# BSK2.net
KiCad netlist of a schematic drawn in EAGLE
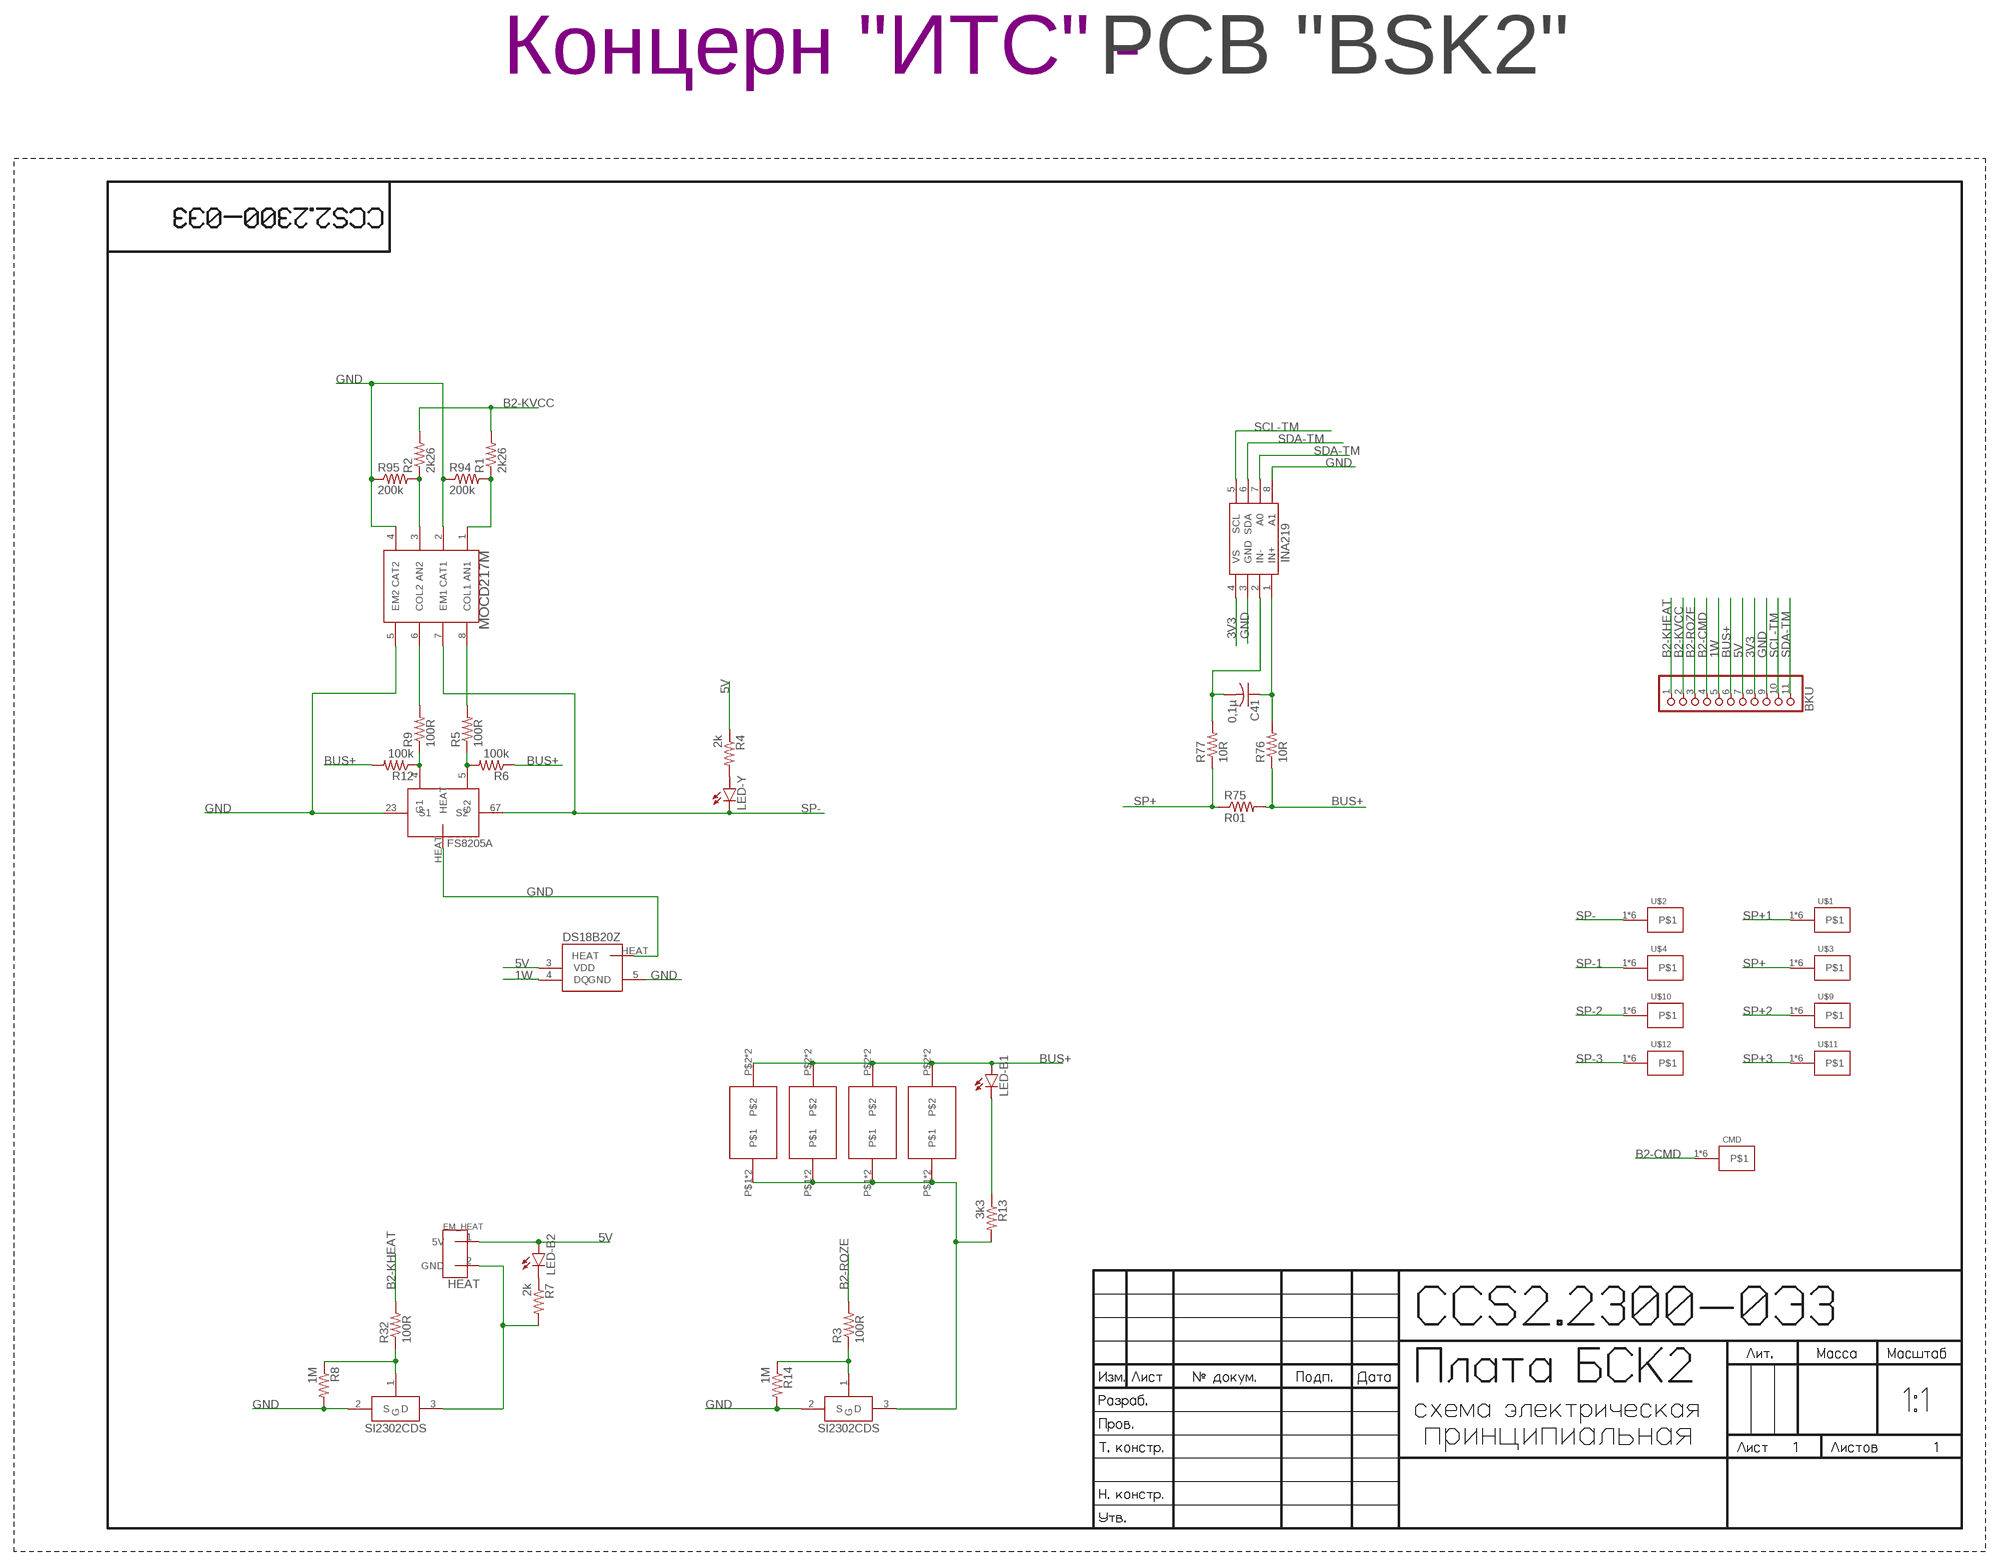
[diagram p0: schematic, sheet 1]

(export (version "E")
  (design (tool "Eeschema 10.0.6"))
  (components
    (comp (ref "BKU")
      (value "PINHD-1X11")
      (footprint "eagle-import:1X11")
      (libsource (lib "eagle-import") (part "PINHD-1X11"))
    )
    (comp (ref "C41")
      (value "0,1µ")
      (footprint "eagle-import:C0603")
      (libsource (lib "eagle-import") (part "C-USC0603"))
    )
    (comp (ref "CMD")
      (value "KCONNECTQUAD")
      (footprint "eagle-import:KCONNECT_QUAD")
      (libsource (lib "eagle-import") (part "KCONNECTQUAD"))
    )
    (comp (ref "DS18B20Z1")
      (value "DS18B20Z")
      (footprint "eagle-import:SOIC8+HEAT_S")
      (libsource (lib "eagle-import") (part "DS18B20Z"))
    )
    (comp (ref "INA")
      (value "INA219AID")
      (footprint "eagle-import:SOT23-8")
      (libsource (lib "eagle-import") (part "INA219AID"))
    )
    (comp (ref "LED-B1")
      (value "LEDCHIPLED_0603")
      (footprint "eagle-import:CHIPLED_0603")
      (libsource (lib "eagle-import") (part "LEDCHIPLED_0603"))
    )
    (comp (ref "LED-B2")
      (value "LEDCHIPLED_0603")
      (footprint "eagle-import:CHIPLED_0603")
      (libsource (lib "eagle-import") (part "LEDCHIPLED_0603"))
    )
    (comp (ref "LED-Y")
      (value "LAP4-BOTTOM")
      (footprint "eagle-import:P47F-BOTTOM")
      (libsource (lib "eagle-import") (part "P4-BOTTOMLA"))
    )
    (comp (ref "MOCD")
      (value "MOCD")
      (footprint "eagle-import:SOIC8")
      (libsource (lib "eagle-import") (part "MOCD217M"))
    )
    (comp (ref "R1")
      (value "2k26")
      (footprint "eagle-import:R0603")
      (libsource (lib "eagle-import") (part "resistor_348_R-US_R0603"))
    )
    (comp (ref "R2")
      (value "2k26")
      (footprint "eagle-import:R0603")
      (libsource (lib "eagle-import") (part "resistor_348_R-US_R0603"))
    )
    (comp (ref "R3")
      (value "100R")
      (footprint "eagle-import:R0603")
      (libsource (lib "eagle-import") (part "resistor_R-US_R0603"))
    )
    (comp (ref "R4")
      (value "2k")
      (footprint "eagle-import:R0603")
      (libsource (lib "eagle-import") (part "resistor_348_R-US_R0603"))
    )
    (comp (ref "R5")
      (value "100R")
      (footprint "eagle-import:R0603")
      (libsource (lib "eagle-import") (part "resistor_348_R-US_R0603"))
    )
    (comp (ref "R6")
      (value "100k")
      (footprint "eagle-import:R0603")
      (libsource (lib "eagle-import") (part "resistor_348_R-US_R0603"))
    )
    (comp (ref "R7")
      (value "2k")
      (footprint "eagle-import:R0603")
      (libsource (lib "eagle-import") (part "resistor_348_R-US_R0603"))
    )
    (comp (ref "R8")
      (value "1M")
      (footprint "eagle-import:R0603")
      (libsource (lib "eagle-import") (part "resistor_348_R-US_R0603"))
    )
    (comp (ref "R9")
      (value "100R")
      (footprint "eagle-import:R0603")
      (libsource (lib "eagle-import") (part "resistor_348_R-US_R0603"))
    )
    (comp (ref "R12")
      (value "100k")
      (footprint "eagle-import:R0603")
      (libsource (lib "eagle-import") (part "resistor_348_R-US_R0603"))
    )
    (comp (ref "R13")
      (value "3k3")
      (footprint "eagle-import:R0603")
      (libsource (lib "eagle-import") (part "resistor_348_R-US_R0603"))
    )
    (comp (ref "R14")
      (value "1M")
      (footprint "eagle-import:R0603")
      (libsource (lib "eagle-import") (part "resistor_348_R-US_R0603"))
    )
    (comp (ref "R32")
      (value "100R")
      (footprint "eagle-import:R0603")
      (libsource (lib "eagle-import") (part "resistor_R-US_R0603"))
    )
    (comp (ref "R75")
      (value "R01")
      (footprint "eagle-import:R2512")
      (libsource (lib "eagle-import") (part "R-US_R2512"))
    )
    (comp (ref "R76")
      (value "10R")
      (footprint "eagle-import:R0603")
      (libsource (lib "eagle-import") (part "resistor_R-US_R0603"))
    )
    (comp (ref "R77")
      (value "10R")
      (footprint "eagle-import:R0603")
      (libsource (lib "eagle-import") (part "resistor_R-US_R0603"))
    )
    (comp (ref "R94")
      (value "200k")
      (footprint "eagle-import:R0603")
      (libsource (lib "eagle-import") (part "resistor_348_R-US_R0603"))
    )
    (comp (ref "R95")
      (value "200k")
      (footprint "eagle-import:R0603")
      (libsource (lib "eagle-import") (part "resistor_348_R-US_R0603"))
    )
    (comp (ref "U$1")
      (value "KCONNECT")
      (footprint "eagle-import:KCONNECT")
      (libsource (lib "eagle-import") (part "KCONNECT"))
    )
    (comp (ref "U$2")
      (value "KCONNECT")
      (footprint "eagle-import:KCONNECT")
      (libsource (lib "eagle-import") (part "KCONNECT"))
    )
    (comp (ref "U$3")
      (value "KCONNECT")
      (footprint "eagle-import:KCONNECT")
      (libsource (lib "eagle-import") (part "KCONNECT"))
    )
    (comp (ref "U$4")
      (value "KCONNECT")
      (footprint "eagle-import:KCONNECT")
      (libsource (lib "eagle-import") (part "KCONNECT"))
    )
    (comp (ref "U$6")
      (value "GRAFITGRAFIT4_2")
      (footprint "eagle-import:GRAFIT4_2")
      (libsource (lib "eagle-import") (part "GRAFITGRAFIT4_2"))
    )
    (comp (ref "U$7")
      (value "GRAFITGRAFIT4_2")
      (footprint "eagle-import:GRAFIT4_2")
      (libsource (lib "eagle-import") (part "GRAFITGRAFIT4_2"))
    )
    (comp (ref "U$8")
      (value "SI2302CDS")
      (footprint "eagle-import:SOT23-3")
      (libsource (lib "eagle-import") (part "SI2302CDS"))
    )
    (comp (ref "U$9")
      (value "KCONNECT")
      (footprint "eagle-import:KCONNECT")
      (libsource (lib "eagle-import") (part "KCONNECT"))
    )
    (comp (ref "U$10")
      (value "KCONNECT")
      (footprint "eagle-import:KCONNECT")
      (libsource (lib "eagle-import") (part "KCONNECT"))
    )
    (comp (ref "U$11")
      (value "KCONNECT")
      (footprint "eagle-import:KCONNECT")
      (libsource (lib "eagle-import") (part "KCONNECT"))
    )
    (comp (ref "U$12")
      (value "KCONNECT")
      (footprint "eagle-import:KCONNECT")
      (libsource (lib "eagle-import") (part "KCONNECT"))
    )
    (comp (ref "U$13")
      (value "SI2302CDS")
      (footprint "eagle-import:SOT23-3")
      (libsource (lib "eagle-import") (part "SI2302CDS"))
    )
    (comp (ref "U$14")
      (value "EM_HEAT")
      (footprint "eagle-import:EM_HEAT")
      (libsource (lib "eagle-import") (part "EM_HEAT"))
    )
    (comp (ref "U$15")
      (value "GRAFITGRAFIT4_2")
      (footprint "eagle-import:GRAFIT4_2")
      (libsource (lib "eagle-import") (part "GRAFITGRAFIT4_2"))
    )
    (comp (ref "U$16")
      (value "GRAFITGRAFIT4_2")
      (footprint "eagle-import:GRAFIT4_2")
      (libsource (lib "eagle-import") (part "GRAFITGRAFIT4_2"))
    )
    (comp (ref "U$17")
      (value "PCB \"BSK2\"")
      (footprint "eagle-import:ITS-LOGO")
      (libsource (lib "eagle-import") (part "ITS-LOGOPCB-{dblquote}{dblquote}"))
    )
    (comp (ref "U$26")
      (value "FS8205A+")
      (footprint "eagle-import:FS8205A+")
      (libsource (lib "eagle-import") (part "FS8205A+"))
    )
  )
  (nets
    (net (code "1") (name "/1W") (class "Default")
      (node (ref "BKU") (pin "5") (pinfunction "5_5") (pintype "passive"))
      (node (ref "DS18B20Z1") (pin "4") (pinfunction "DQ_4") (pintype "bidirectional"))
    )
    (net (code "2") (name "/3V3") (class "Default")
      (node (ref "BKU") (pin "8") (pinfunction "8_8") (pintype "passive"))
      (node (ref "INA") (pin "4") (pinfunction "VS_4") (pintype "bidirectional"))
    )
    (net (code "3") (name "/5V") (class "Default")
      (node (ref "BKU") (pin "7") (pinfunction "7_7") (pintype "passive"))
      (node (ref "DS18B20Z1") (pin "3") (pinfunction "VDD_3") (pintype "bidirectional"))
      (node (ref "LED-B2") (pin "A") (pinfunction "A_A") (pintype "passive"))
      (node (ref "R4") (pin "1") (pinfunction "1_1") (pintype "passive"))
      (node (ref "U$14") (pin "1") (pinfunction "5V_1") (pintype "bidirectional"))
    )
    (net (code "4") (name "/B2-CMD") (class "Default")
      (node (ref "BKU") (pin "4") (pinfunction "4_4") (pintype "passive"))
      (node (ref "CMD") (pin "1") (pinfunction "P$1_1") (pintype "bidirectional"))
      (node (ref "CMD") (pin "2") (pinfunction "P$1_2") (pintype "bidirectional"))
      (node (ref "CMD") (pin "3") (pinfunction "P$1_3") (pintype "bidirectional"))
      (node (ref "CMD") (pin "4") (pinfunction "P$1_4") (pintype "bidirectional"))
      (node (ref "CMD") (pin "P$1") (pinfunction "P$1_P$1") (pintype "bidirectional"))
      (node (ref "CMD") (pin "P$2") (pinfunction "P$1_P$2") (pintype "bidirectional"))
    )
    (net (code "5") (name "/B2-KHEAT") (class "Default")
      (node (ref "BKU") (pin "1") (pinfunction "1_1") (pintype "passive"))
      (node (ref "R32") (pin "2") (pinfunction "2_2") (pintype "passive"))
    )
    (net (code "6") (name "/B2-KVCC") (class "Default")
      (node (ref "BKU") (pin "2") (pinfunction "2_2") (pintype "passive"))
      (node (ref "R1") (pin "2") (pinfunction "2_2") (pintype "passive"))
      (node (ref "R2") (pin "2") (pinfunction "2_2") (pintype "passive"))
    )
    (net (code "7") (name "/B2-ROZE") (class "Default")
      (node (ref "BKU") (pin "3") (pinfunction "3_3") (pintype "passive"))
      (node (ref "R3") (pin "2") (pinfunction "2_2") (pintype "passive"))
    )
    (net (code "8") (name "/BUS+") (class "Default")
      (node (ref "BKU") (pin "6") (pinfunction "6_6") (pintype "passive"))
      (node (ref "LED-B1") (pin "A") (pinfunction "A_A") (pintype "passive"))
      (node (ref "R12") (pin "2") (pinfunction "2_2") (pintype "passive"))
      (node (ref "R6") (pin "1") (pinfunction "1_1") (pintype "passive"))
      (node (ref "R75") (pin "2") (pinfunction "2_2") (pintype "passive"))
      (node (ref "R76") (pin "1") (pinfunction "1_1") (pintype "passive"))
      (node (ref "U$15") (pin "P$2") (pinfunction "P$2_P$2") (pintype "bidirectional"))
      (node (ref "U$15") (pin "P$5") (pinfunction "P$2_P$5") (pintype "bidirectional"))
      (node (ref "U$16") (pin "P$2") (pinfunction "P$2_P$2") (pintype "bidirectional"))
      (node (ref "U$16") (pin "P$5") (pinfunction "P$2_P$5") (pintype "bidirectional"))
      (node (ref "U$6") (pin "P$2") (pinfunction "P$2_P$2") (pintype "bidirectional"))
      (node (ref "U$6") (pin "P$5") (pinfunction "P$2_P$5") (pintype "bidirectional"))
      (node (ref "U$7") (pin "P$2") (pinfunction "P$2_P$2") (pintype "bidirectional"))
      (node (ref "U$7") (pin "P$5") (pinfunction "P$2_P$5") (pintype "bidirectional"))
    )
    (net (code "9") (name "/GND") (class "Default")
      (node (ref "BKU") (pin "9") (pinfunction "9_9") (pintype "passive"))
      (node (ref "DS18B20Z1") (pin "5") (pinfunction "GND_5") (pintype "bidirectional"))
      (node (ref "DS18B20Z1") (pin "HEAT") (pinfunction "HEAT_HEAT") (pintype "bidirectional"))
      (node (ref "INA") (pin "3") (pinfunction "GND_3") (pintype "bidirectional"))
      (node (ref "INA") (pin "8") (pinfunction "A1_8") (pintype "bidirectional"))
      (node (ref "MOCD") (pin "2") (pinfunction "CAT1_2") (pintype "bidirectional"))
      (node (ref "MOCD") (pin "4") (pinfunction "CAT2_4") (pintype "bidirectional"))
      (node (ref "MOCD") (pin "5") (pinfunction "EM2_5") (pintype "bidirectional"))
      (node (ref "R14") (pin "2") (pinfunction "2_2") (pintype "passive"))
      (node (ref "R8") (pin "2") (pinfunction "2_2") (pintype "passive"))
      (node (ref "R94") (pin "1") (pinfunction "1_1") (pintype "passive"))
      (node (ref "R95") (pin "1") (pinfunction "1_1") (pintype "passive"))
      (node (ref "U$13") (pin "2") (pinfunction "S_2") (pintype "bidirectional"))
      (node (ref "U$26") (pin "23") (pinfunction "S1_23") (pintype "bidirectional"))
      (node (ref "U$26") (pin "HEAT") (pinfunction "HEAT_HEAT") (pintype "bidirectional"))
      (node (ref "U$8") (pin "2") (pinfunction "S_2") (pintype "bidirectional"))
    )
    (net (code "10") (name "/SCL-TM") (class "Default")
      (node (ref "BKU") (pin "10") (pinfunction "10_10") (pintype "passive"))
      (node (ref "INA") (pin "5") (pinfunction "SCL_5") (pintype "bidirectional"))
    )
    (net (code "11") (name "/SDA-TM") (class "Default")
      (node (ref "BKU") (pin "11") (pinfunction "11_11") (pintype "passive"))
      (node (ref "INA") (pin "6") (pinfunction "SDA_6") (pintype "bidirectional"))
      (node (ref "INA") (pin "7") (pinfunction "A0_7") (pintype "bidirectional"))
    )
    (net (code "12") (name "/SP+") (class "Default")
      (node (ref "R75") (pin "1") (pinfunction "1_1") (pintype "passive"))
      (node (ref "R77") (pin "1") (pinfunction "1_1") (pintype "passive"))
      (node (ref "U$3") (pin "1") (pinfunction "P$1_1") (pintype "bidirectional"))
      (node (ref "U$3") (pin "2") (pinfunction "P$1_2") (pintype "bidirectional"))
      (node (ref "U$3") (pin "3") (pinfunction "P$1_3") (pintype "bidirectional"))
      (node (ref "U$3") (pin "4") (pinfunction "P$1_4") (pintype "bidirectional"))
      (node (ref "U$3") (pin "P$1") (pinfunction "P$1_P$1") (pintype "bidirectional"))
      (node (ref "U$3") (pin "P$2") (pinfunction "P$1_P$2") (pintype "bidirectional"))
    )
    (net (code "13") (name "/SP+1") (class "Default")
      (node (ref "U$1") (pin "1") (pinfunction "P$1_1") (pintype "bidirectional"))
      (node (ref "U$1") (pin "2") (pinfunction "P$1_2") (pintype "bidirectional"))
      (node (ref "U$1") (pin "3") (pinfunction "P$1_3") (pintype "bidirectional"))
      (node (ref "U$1") (pin "4") (pinfunction "P$1_4") (pintype "bidirectional"))
      (node (ref "U$1") (pin "P$1") (pinfunction "P$1_P$1") (pintype "bidirectional"))
      (node (ref "U$1") (pin "P$2") (pinfunction "P$1_P$2") (pintype "bidirectional"))
    )
    (net (code "14") (name "/SP+2") (class "Default")
      (node (ref "U$9") (pin "1") (pinfunction "P$1_1") (pintype "bidirectional"))
      (node (ref "U$9") (pin "2") (pinfunction "P$1_2") (pintype "bidirectional"))
      (node (ref "U$9") (pin "3") (pinfunction "P$1_3") (pintype "bidirectional"))
      (node (ref "U$9") (pin "4") (pinfunction "P$1_4") (pintype "bidirectional"))
      (node (ref "U$9") (pin "P$1") (pinfunction "P$1_P$1") (pintype "bidirectional"))
      (node (ref "U$9") (pin "P$2") (pinfunction "P$1_P$2") (pintype "bidirectional"))
    )
    (net (code "15") (name "/SP+3") (class "Default")
      (node (ref "U$11") (pin "1") (pinfunction "P$1_1") (pintype "bidirectional"))
      (node (ref "U$11") (pin "2") (pinfunction "P$1_2") (pintype "bidirectional"))
      (node (ref "U$11") (pin "3") (pinfunction "P$1_3") (pintype "bidirectional"))
      (node (ref "U$11") (pin "4") (pinfunction "P$1_4") (pintype "bidirectional"))
      (node (ref "U$11") (pin "P$1") (pinfunction "P$1_P$1") (pintype "bidirectional"))
      (node (ref "U$11") (pin "P$2") (pinfunction "P$1_P$2") (pintype "bidirectional"))
    )
    (net (code "16") (name "/SP-") (class "Default")
      (node (ref "LED-Y") (pin "C") (pinfunction "C_C") (pintype "passive"))
      (node (ref "MOCD") (pin "7") (pinfunction "EM1_7") (pintype "bidirectional"))
      (node (ref "U$2") (pin "1") (pinfunction "P$1_1") (pintype "bidirectional"))
      (node (ref "U$2") (pin "2") (pinfunction "P$1_2") (pintype "bidirectional"))
      (node (ref "U$2") (pin "3") (pinfunction "P$1_3") (pintype "bidirectional"))
      (node (ref "U$2") (pin "4") (pinfunction "P$1_4") (pintype "bidirectional"))
      (node (ref "U$2") (pin "P$1") (pinfunction "P$1_P$1") (pintype "bidirectional"))
      (node (ref "U$2") (pin "P$2") (pinfunction "P$1_P$2") (pintype "bidirectional"))
      (node (ref "U$26") (pin "67") (pinfunction "S2_67") (pintype "bidirectional"))
    )
    (net (code "17") (name "/SP-1") (class "Default")
      (node (ref "U$4") (pin "1") (pinfunction "P$1_1") (pintype "bidirectional"))
      (node (ref "U$4") (pin "2") (pinfunction "P$1_2") (pintype "bidirectional"))
      (node (ref "U$4") (pin "3") (pinfunction "P$1_3") (pintype "bidirectional"))
      (node (ref "U$4") (pin "4") (pinfunction "P$1_4") (pintype "bidirectional"))
      (node (ref "U$4") (pin "P$1") (pinfunction "P$1_P$1") (pintype "bidirectional"))
      (node (ref "U$4") (pin "P$2") (pinfunction "P$1_P$2") (pintype "bidirectional"))
    )
    (net (code "18") (name "/SP-2") (class "Default")
      (node (ref "U$10") (pin "1") (pinfunction "P$1_1") (pintype "bidirectional"))
      (node (ref "U$10") (pin "2") (pinfunction "P$1_2") (pintype "bidirectional"))
      (node (ref "U$10") (pin "3") (pinfunction "P$1_3") (pintype "bidirectional"))
      (node (ref "U$10") (pin "4") (pinfunction "P$1_4") (pintype "bidirectional"))
      (node (ref "U$10") (pin "P$1") (pinfunction "P$1_P$1") (pintype "bidirectional"))
      (node (ref "U$10") (pin "P$2") (pinfunction "P$1_P$2") (pintype "bidirectional"))
    )
    (net (code "19") (name "/SP-3") (class "Default")
      (node (ref "U$12") (pin "1") (pinfunction "P$1_1") (pintype "bidirectional"))
      (node (ref "U$12") (pin "2") (pinfunction "P$1_2") (pintype "bidirectional"))
      (node (ref "U$12") (pin "3") (pinfunction "P$1_3") (pintype "bidirectional"))
      (node (ref "U$12") (pin "4") (pinfunction "P$1_4") (pintype "bidirectional"))
      (node (ref "U$12") (pin "P$1") (pinfunction "P$1_P$1") (pintype "bidirectional"))
      (node (ref "U$12") (pin "P$2") (pinfunction "P$1_P$2") (pintype "bidirectional"))
    )
    (net (code "20") (name "Net-(INA-IN+)") (class "Default")
      (node (ref "C41") (pin "1") (pinfunction "1_1") (pintype "passive"))
      (node (ref "INA") (pin "1") (pinfunction "IN+_1") (pintype "bidirectional"))
      (node (ref "R76") (pin "2") (pinfunction "2_2") (pintype "passive"))
    )
    (net (code "21") (name "Net-(INA-IN-)") (class "Default")
      (node (ref "C41") (pin "2") (pinfunction "2_2") (pintype "passive"))
      (node (ref "INA") (pin "2") (pinfunction "IN-_2") (pintype "bidirectional"))
      (node (ref "R77") (pin "2") (pinfunction "2_2") (pintype "passive"))
    )
    (net (code "22") (name "Net-(LED-B1-PadC)") (class "Default")
      (node (ref "LED-B1") (pin "C") (pinfunction "C_C") (pintype "passive"))
      (node (ref "R13") (pin "1") (pinfunction "1_1") (pintype "passive"))
    )
    (net (code "23") (name "Net-(LED-B2-PadC)") (class "Default")
      (node (ref "LED-B2") (pin "C") (pinfunction "C_C") (pintype "passive"))
      (node (ref "R7") (pin "1") (pinfunction "1_1") (pintype "passive"))
    )
    (net (code "24") (name "Net-(LED-Y-PadA)") (class "Default")
      (node (ref "LED-Y") (pin "A") (pinfunction "A_A") (pintype "passive"))
      (node (ref "R4") (pin "2") (pinfunction "2_2") (pintype "passive"))
    )
    (net (code "25") (name "Net-(MOCD-AN1)") (class "Default")
      (node (ref "MOCD") (pin "1") (pinfunction "AN1_1") (pintype "bidirectional"))
      (node (ref "R1") (pin "1") (pinfunction "1_1") (pintype "passive"))
      (node (ref "R94") (pin "2") (pinfunction "2_2") (pintype "passive"))
    )
    (net (code "26") (name "Net-(MOCD-AN2)") (class "Default")
      (node (ref "MOCD") (pin "3") (pinfunction "AN2_3") (pintype "bidirectional"))
      (node (ref "R2") (pin "1") (pinfunction "1_1") (pintype "passive"))
      (node (ref "R95") (pin "2") (pinfunction "2_2") (pintype "passive"))
    )
    (net (code "27") (name "Net-(MOCD-COL1)") (class "Default")
      (node (ref "MOCD") (pin "8") (pinfunction "COL1_8") (pintype "bidirectional"))
      (node (ref "R5") (pin "2") (pinfunction "2_2") (pintype "passive"))
    )
    (net (code "28") (name "Net-(MOCD-COL2)") (class "Default")
      (node (ref "MOCD") (pin "6") (pinfunction "COL2_6") (pintype "bidirectional"))
      (node (ref "R9") (pin "2") (pinfunction "2_2") (pintype "passive"))
    )
    (net (code "29") (name "Net-(U$8-G)") (class "Default")
      (node (ref "R32") (pin "1") (pinfunction "1_1") (pintype "passive"))
      (node (ref "R8") (pin "1") (pinfunction "1_1") (pintype "passive"))
      (node (ref "U$8") (pin "1") (pinfunction "G_1") (pintype "bidirectional"))
    )
    (net (code "30") (name "Net-(U$13-D)") (class "Default")
      (node (ref "R13") (pin "2") (pinfunction "2_2") (pintype "passive"))
      (node (ref "U$13") (pin "3") (pinfunction "D_3") (pintype "bidirectional"))
      (node (ref "U$15") (pin "P$1") (pinfunction "P$1_P$1") (pintype "bidirectional"))
      (node (ref "U$15") (pin "P$4") (pinfunction "P$1_P$4") (pintype "bidirectional"))
      (node (ref "U$16") (pin "P$1") (pinfunction "P$1_P$1") (pintype "bidirectional"))
      (node (ref "U$16") (pin "P$4") (pinfunction "P$1_P$4") (pintype "bidirectional"))
      (node (ref "U$6") (pin "P$1") (pinfunction "P$1_P$1") (pintype "bidirectional"))
      (node (ref "U$6") (pin "P$4") (pinfunction "P$1_P$4") (pintype "bidirectional"))
      (node (ref "U$7") (pin "P$1") (pinfunction "P$1_P$1") (pintype "bidirectional"))
      (node (ref "U$7") (pin "P$4") (pinfunction "P$1_P$4") (pintype "bidirectional"))
    )
    (net (code "31") (name "Net-(U$13-G)") (class "Default")
      (node (ref "R14") (pin "1") (pinfunction "1_1") (pintype "passive"))
      (node (ref "R3") (pin "1") (pinfunction "1_1") (pintype "passive"))
      (node (ref "U$13") (pin "1") (pinfunction "G_1") (pintype "bidirectional"))
    )
    (net (code "32") (name "Net-(U$14-GND)") (class "Default")
      (node (ref "R7") (pin "2") (pinfunction "2_2") (pintype "passive"))
      (node (ref "U$14") (pin "2") (pinfunction "GND_2") (pintype "bidirectional"))
      (node (ref "U$8") (pin "3") (pinfunction "D_3") (pintype "bidirectional"))
    )
    (net (code "33") (name "Net-(U$26-G1)") (class "Default")
      (node (ref "R12") (pin "1") (pinfunction "1_1") (pintype "passive"))
      (node (ref "R9") (pin "1") (pinfunction "1_1") (pintype "passive"))
      (node (ref "U$26") (pin "4") (pinfunction "G1_4") (pintype "bidirectional"))
    )
    (net (code "34") (name "Net-(U$26-G2)") (class "Default")
      (node (ref "R5") (pin "1") (pinfunction "1_1") (pintype "passive"))
      (node (ref "R6") (pin "2") (pinfunction "2_2") (pintype "passive"))
      (node (ref "U$26") (pin "5") (pinfunction "G2_5") (pintype "bidirectional"))
    )
  )
)
